# Processor.net
KiCad netlist of a schematic drawn in Altium Designer
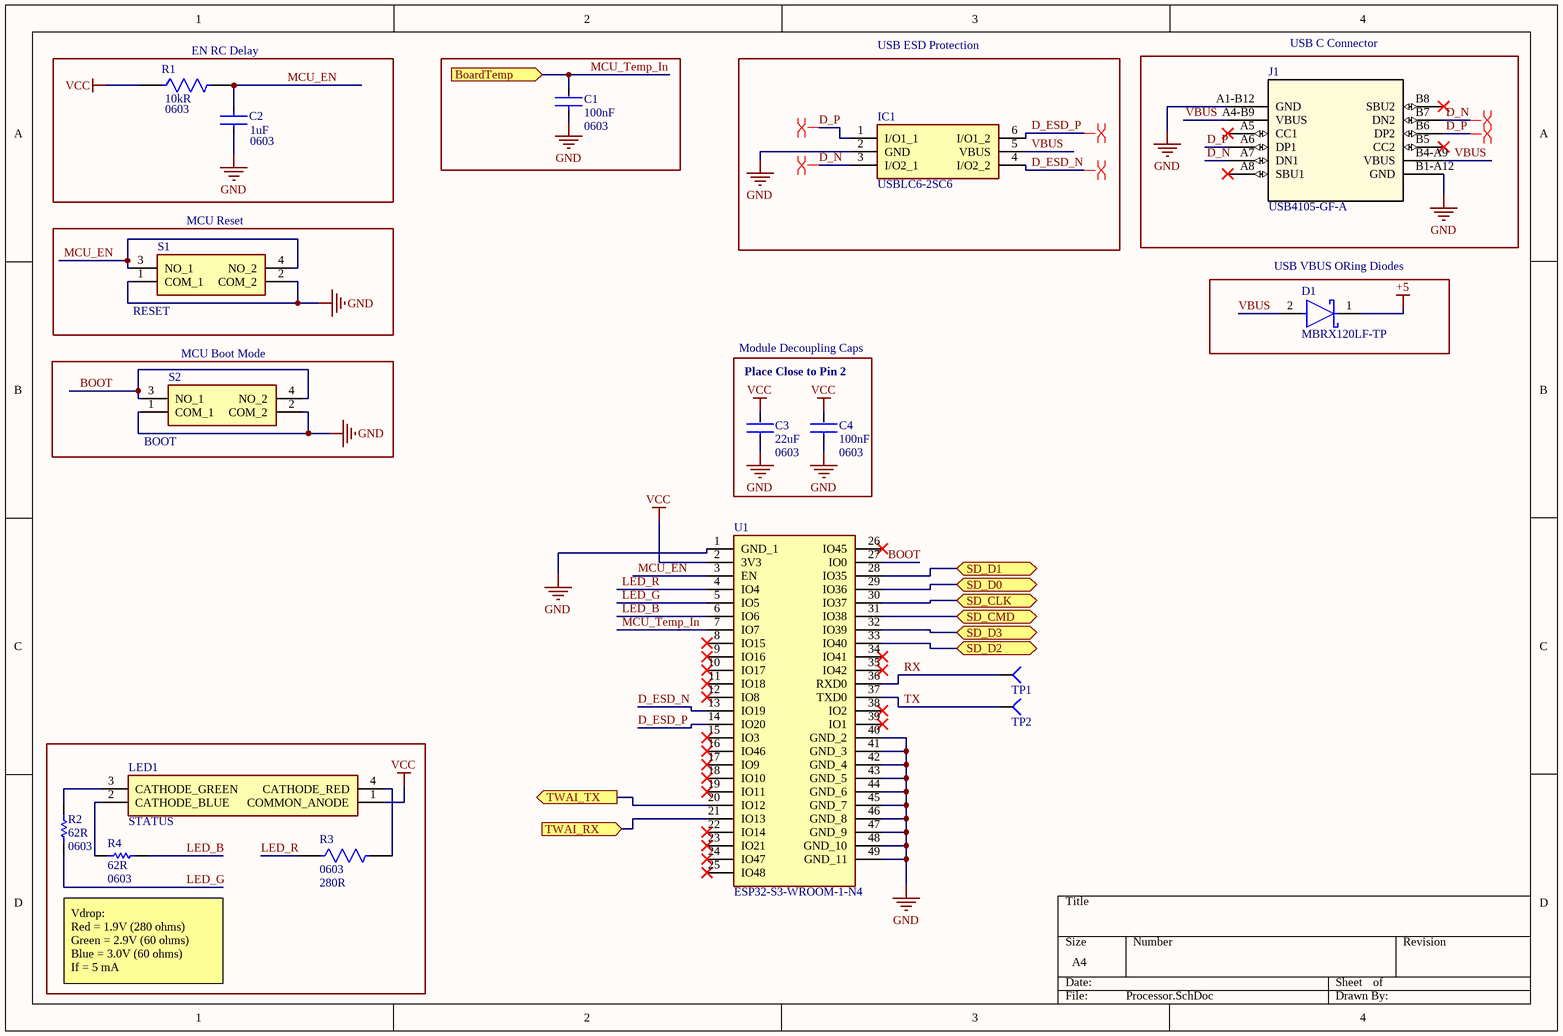
[diagram p0: Processor.SchDoc]

(export (version "E")
  (design (tool "Eeschema 10.0.6"))
  (components
    (comp (ref "C1")
      (value "CL10B104KB8WPNC")
      (footprint "FP-CL10-IPC_A")
      (description "Cap Ceramic 100nF 50V X7R ±10% Pad SMD 0603 +125°C T/R")
      (fields
        (field (name "CAPACITANCE") "100nF")
        (field (name "CASE/PACKAGE") "0603")
        (field (name "TOLERANCE") "10%")
      )
      (libsource (lib "Altium Content Vault") (part "b4654b650e69147ec39a6b967a45e02"))
    )
    (comp (ref "C2")
      (value "UMK107BJ105KA-T")
      (footprint "FP-0603-L_1_6_0_1-W_0_8_0-IPC_A")
      (description "None")
      (fields
        (field (name "TOLERANCE") "10%")
        (field (name "CASE/PACKAGE") "0603")
        (field (name "CAPACITANCE") "1uF")
      )
      (libsource (lib "Altium Content Vault") (part "02cd4be3c70576c341d710602a673aa"))
    )
    (comp (ref "C3")
      (value "GRM188R61A226ME15D")
      (footprint "FP-GRM188-0_2-IPC_C")
      (description "Chip Multilayer Ceramic Capacitors for General Purpose, 0603, 22uF, X5R, 15%, 20%, 10V")
      (fields
        (field (name "TOLERANCE") "20%")
        (field (name "CAPACITANCE") "22uF")
        (field (name "CASE CODE (IMPERIAL)") "0603")
      )
      (libsource (lib "Altium Content Vault") (part "11868f565c42a9108669ba33697ecf6"))
    )
    (comp (ref "C4")
      (value "CL10B104KB8WPNC")
      (footprint "FP-CL10-IPC_A")
      (description "Cap Ceramic 100nF 50V X7R ±10% Pad SMD 0603 +125°C T/R")
      (fields
        (field (name "CAPACITANCE") "100nF")
        (field (name "CASE/PACKAGE") "0603")
        (field (name "TOLERANCE") "10%")
      )
      (libsource (lib "Altium Content Vault") (part "b4654b650e69147ec39a6b967a45e02"))
    )
    (comp (ref "D1")
      (value "MBRX120LF-TP")
      (footprint "FP-SOD-123-IPC_A")
      (description "DIODE SCHOTTKY 20V 1A SOD123")
      (libsource (lib "Altium Content Vault") (part "1d6ec82d83fb6aee721767c19dac4b9"))
    )
    (comp (ref "IC1")
      (value "USBLC6-2SC6")
      (footprint "SOT95P280X145-6N")
      (description "Integrated Circuit")
      (fields (field (name "MOUSER PART NUMBER") "511-USBLC6-2SC6"))
      (libsource (lib "WiCAN_lib") (part "USBLC6-2SC6"))
    )
    (comp (ref "J1")
      (value "USB4105-GF-A")
      (footprint "USB4105_GCT")
      (description "No Description Available")
      (fields (field (name "COPYRIGHT") "Copyright (C) 2022 Ultra Librarian. All rights reserved."))
      (libsource (lib "WiCAN_lib") (part "USB4105-GF-A"))
    )
    (comp (ref "LED1")
      (value "STATUS")
      (footprint "CLMVCFKACL1D1L71BB7C3C3")
      (description "LED")
      (fields
        (field (name "MANUFACTURER_PART_NUMBER") "CLMVC-FKA-CL1D1L71BB7C3C3")
        (field (name "MOUSER PART NUMBER") "941-CLMVCFKACL1D1L71")
      )
      (libsource (lib "WiCAN_lib") (part "CLMVC-FKA-CL1D1L71BB7C3C3"))
    )
    (comp (ref "R1")
      (value "RMCF0603JG10K0")
      (footprint "FP-RMCF0603-MFG")
      (description "10kΩ ±5% 0.1W 0603 Thick Film Chip Resistor AEC-Q200 compliant")
      (fields
        (field (name "TOLERANCE") "5%")
        (field (name "CASE CODE (IMPERIAL)") "0603")
        (field (name "RESISTANCE") "10kR")
      )
      (libsource (lib "Altium Content Vault") (part "1029c3af85768c4190bb7ad29bc67b5"))
    )
    (comp (ref "R2")
      (value "ERJ-3GEYJ620V")
      (footprint "RESC1608X55X30ML15T15")
      (fields
        (field (name "MANUFACTURER") "Panasonic")
        (field (name "RESISTANCE") "62R")
        (field (name "PACKAGE") "0603")
      )
      (libsource (lib "Altium Content Vault") (part "RES"))
    )
    (comp (ref "R3")
      (value "RMCF0603FT280R")
      (footprint "FP-RMCF0603-MFG")
      (description "280Ω ±1% 0.1W 0603 Thick Film Chip Resistor AEC-Q200 compliant")
      (fields
        (field (name "CASE/PACKAGE") "0603")
        (field (name "TOLERANCE") "1%")
        (field (name "RESISTANCE") "280R")
      )
      (libsource (lib "Altium Content Vault") (part "1029c3af85768c4190bb7ad29bc67b5"))
    )
    (comp (ref "R4")
      (value "ERJ-3GEYJ620V")
      (footprint "RESC1608X55X30ML15T15")
      (fields
        (field (name "MANUFACTURER") "Panasonic")
        (field (name "RESISTANCE") "62R")
        (field (name "PACKAGE") "0603")
      )
      (libsource (lib "Altium Content Vault") (part "RES"))
    )
    (comp (ref "S1")
      (value "RESET")
      (footprint "PTS526SKG15SMTR2LFS")
      (description "Switch")
      (fields
        (field (name "MANUFACTURER_PART_NUMBER") "PTS526 SK08 SMTR2 LFS")
        (field (name "MOUSER PART NUMBER") "611-PTS526SK08SMTR2L")
      )
      (libsource (lib "WiCAN_lib") (part "PTS526_SK08_SMTR2_LFS"))
    )
    (comp (ref "S2")
      (value "BOOT")
      (footprint "PTS526SKG15SMTR2LFS")
      (description "Switch")
      (fields
        (field (name "MANUFACTURER_PART_NUMBER") "PTS526 SK08 SMTR2 LFS")
        (field (name "MOUSER PART NUMBER") "611-PTS526SK08SMTR2L")
      )
      (libsource (lib "WiCAN_lib") (part "PTS526_SK08_SMTR2_LFS"))
    )
    (comp (ref "TP1")
      (value "RX")
      (footprint "TESTPOINT_CIRCLE_1MM")
      (description "TESTPOINT 1MM CIRCLE")
      (libsource (lib "Connectors and Headers") (part "TESTPOINT_1MM_CIRCLE"))
    )
    (comp (ref "TP2")
      (value "TX")
      (footprint "TESTPOINT_CIRCLE_1MM")
      (description "TESTPOINT 1MM CIRCLE")
      (libsource (lib "Connectors and Headers") (part "TESTPOINT_1MM_CIRCLE"))
    )
    (comp (ref "U1")
      (value "ESP32-S3-WROOM-1-N4")
      (footprint "ESP32S3WROOM1N4")
      (description "Integrated Circuit")
      (fields (field (name "MOUSER PART NUMBER") "356-ESP32-S3WROOM1N4"))
      (libsource (lib "WiCAN_lib") (part "ESP32-S3-WROOM-1-N4"))
    )
  )
  (nets
    (net (code "1") (name "+5") (class "Default")
      (node (ref "D1") (pin "1") (pinfunction "C_1") (pintype "passive"))
    )
    (net (code "2") (name "/BOOT") (class "Default")
      (node (ref "S2") (pin "3") (pinfunction "NO_1_3") (pintype "passive"))
      (node (ref "S2") (pin "4") (pinfunction "NO_2_4") (pintype "passive"))
      (node (ref "U1") (pin "27") (pinfunction "IO0_27") (pintype "passive"))
    )
    (net (code "3") (name "/D_ESD_N") (class "Default")
      (node (ref "IC1") (pin "4") (pinfunction "I/O2_2_4") (pintype "passive"))
      (node (ref "U1") (pin "13") (pinfunction "IO19_13") (pintype "passive"))
    )
    (net (code "4") (name "/D_ESD_P") (class "Default")
      (node (ref "IC1") (pin "6") (pinfunction "I/O1_2_6") (pintype "passive"))
      (node (ref "U1") (pin "14") (pinfunction "IO20_14") (pintype "passive"))
    )
    (net (code "5") (name "/D_N") (class "Default")
      (node (ref "IC1") (pin "3") (pinfunction "I/O2_1_3") (pintype "passive"))
      (node (ref "J1") (pin "A7") (pinfunction "DN1_A7") (pintype "bidirectional"))
      (node (ref "J1") (pin "B7") (pinfunction "DN2_B7") (pintype "bidirectional"))
    )
    (net (code "6") (name "/D_P") (class "Default")
      (node (ref "IC1") (pin "1") (pinfunction "I/O1_1_1") (pintype "passive"))
      (node (ref "J1") (pin "A6") (pinfunction "DP1_A6") (pintype "bidirectional"))
      (node (ref "J1") (pin "B6") (pinfunction "DP2_B6") (pintype "bidirectional"))
    )
    (net (code "7") (name "/LED_B") (class "Default")
      (node (ref "R4") (pin "2") (pinfunction "2_2") (pintype "passive"))
      (node (ref "U1") (pin "6") (pinfunction "IO6_6") (pintype "passive"))
    )
    (net (code "8") (name "/LED_G") (class "Default")
      (node (ref "R2") (pin "2") (pinfunction "2_2") (pintype "passive"))
      (node (ref "U1") (pin "5") (pinfunction "IO5_5") (pintype "passive"))
    )
    (net (code "9") (name "/LED_R") (class "Default")
      (node (ref "R3") (pin "1") (pinfunction "1_1") (pintype "passive"))
      (node (ref "U1") (pin "4") (pinfunction "IO4_4") (pintype "passive"))
    )
    (net (code "10") (name "/MCU_EN") (class "Default")
      (node (ref "C2") (pin "1") (pinfunction "1_1") (pintype "passive"))
      (node (ref "R1") (pin "2") (pinfunction "2_2") (pintype "passive"))
      (node (ref "S1") (pin "3") (pinfunction "NO_1_3") (pintype "passive"))
      (node (ref "S1") (pin "4") (pinfunction "NO_2_4") (pintype "passive"))
      (node (ref "U1") (pin "3") (pinfunction "EN_3") (pintype "passive"))
    )
    (net (code "11") (name "/MCU_Temp_In") (class "Default")
      (node (ref "C1") (pin "2") (pinfunction "2_2") (pintype "passive"))
      (node (ref "U1") (pin "7") (pinfunction "IO7_7") (pintype "passive"))
    )
    (net (code "12") (name "/RX") (class "Default")
      (node (ref "TP1") (pin "1") (pinfunction "=value_1") (pintype "passive"))
      (node (ref "U1") (pin "36") (pinfunction "RXD0_36") (pintype "passive"))
    )
    (net (code "13") (name "/SD_CLK") (class "Default")
      (node (ref "U1") (pin "30") (pinfunction "IO37_30") (pintype "passive"))
    )
    (net (code "14") (name "/SD_CMD") (class "Default")
      (node (ref "U1") (pin "31") (pinfunction "IO38_31") (pintype "passive"))
    )
    (net (code "15") (name "/SD_D0") (class "Default")
      (node (ref "U1") (pin "29") (pinfunction "IO36_29") (pintype "passive"))
    )
    (net (code "16") (name "/SD_D1") (class "Default")
      (node (ref "U1") (pin "28") (pinfunction "IO35_28") (pintype "passive"))
    )
    (net (code "17") (name "/SD_D2") (class "Default")
      (node (ref "U1") (pin "33") (pinfunction "IO40_33") (pintype "passive"))
    )
    (net (code "18") (name "/SD_D3") (class "Default")
      (node (ref "U1") (pin "32") (pinfunction "IO39_32") (pintype "passive"))
    )
    (net (code "19") (name "/TWAI_RX") (class "Default")
      (node (ref "U1") (pin "21") (pinfunction "IO13_21") (pintype "passive"))
    )
    (net (code "20") (name "/TWAI_TX") (class "Default")
      (node (ref "U1") (pin "20") (pinfunction "IO12_20") (pintype "passive"))
    )
    (net (code "21") (name "/TX") (class "Default")
      (node (ref "TP2") (pin "1") (pinfunction "=value_1") (pintype "passive"))
      (node (ref "U1") (pin "37") (pinfunction "TXD0_37") (pintype "passive"))
    )
    (net (code "22") (name "/VBUS") (class "Default")
      (node (ref "D1") (pin "2") (pinfunction "A_2") (pintype "passive"))
      (node (ref "IC1") (pin "5") (pinfunction "VBUS_5") (pintype "passive"))
      (node (ref "J1") (pin "A4-B9") (pinfunction "VBUS_A4-B9") (pintype "power_in"))
      (node (ref "J1") (pin "B4-A9") (pinfunction "VBUS_B4-A9") (pintype "power_in"))
    )
    (net (code "23") (name "GND") (class "Default")
      (node (ref "C1") (pin "1") (pinfunction "1_1") (pintype "passive"))
      (node (ref "C2") (pin "2") (pinfunction "2_2") (pintype "passive"))
      (node (ref "C3") (pin "1") (pinfunction "1_1") (pintype "passive"))
      (node (ref "C4") (pin "1") (pinfunction "1_1") (pintype "passive"))
      (node (ref "IC1") (pin "2") (pinfunction "GND_2") (pintype "passive"))
      (node (ref "J1") (pin "A1-B12") (pinfunction "GND_A1-B12") (pintype "passive"))
      (node (ref "J1") (pin "B1-A12") (pinfunction "GND_B1-A12") (pintype "passive"))
      (node (ref "S1") (pin "1") (pinfunction "COM_1_1") (pintype "passive"))
      (node (ref "S1") (pin "2") (pinfunction "COM_2_2") (pintype "passive"))
      (node (ref "S2") (pin "1") (pinfunction "COM_1_1") (pintype "passive"))
      (node (ref "S2") (pin "2") (pinfunction "COM_2_2") (pintype "passive"))
      (node (ref "U1") (pin "1") (pinfunction "GND_1_1") (pintype "passive"))
      (node (ref "U1") (pin "40") (pinfunction "GND_2_40") (pintype "passive"))
      (node (ref "U1") (pin "41") (pinfunction "GND_3_41") (pintype "passive"))
      (node (ref "U1") (pin "42") (pinfunction "GND_4_42") (pintype "passive"))
      (node (ref "U1") (pin "43") (pinfunction "GND_5_43") (pintype "passive"))
      (node (ref "U1") (pin "44") (pinfunction "GND_6_44") (pintype "passive"))
      (node (ref "U1") (pin "45") (pinfunction "GND_7_45") (pintype "passive"))
      (node (ref "U1") (pin "46") (pinfunction "GND_8_46") (pintype "passive"))
      (node (ref "U1") (pin "47") (pinfunction "GND_9_47") (pintype "passive"))
      (node (ref "U1") (pin "48") (pinfunction "GND_10_48") (pintype "passive"))
      (node (ref "U1") (pin "49") (pinfunction "GND_11_49") (pintype "passive"))
    )
    (net (code "24") (name "Net-(LED1-CATHODE_BLUE)") (class "Default")
      (node (ref "LED1") (pin "2") (pinfunction "CATHODE_BLUE_2") (pintype "passive"))
      (node (ref "R4") (pin "1") (pinfunction "1_1") (pintype "passive"))
    )
    (net (code "25") (name "Net-(LED1-CATHODE_GREEN)") (class "Default")
      (node (ref "LED1") (pin "3") (pinfunction "CATHODE_GREEN_3") (pintype "passive"))
      (node (ref "R2") (pin "1") (pinfunction "1_1") (pintype "passive"))
    )
    (net (code "26") (name "Net-(LED1-CATHODE_RED)") (class "Default")
      (node (ref "LED1") (pin "4") (pinfunction "CATHODE_RED_4") (pintype "passive"))
      (node (ref "R3") (pin "2") (pinfunction "2_2") (pintype "passive"))
    )
    (net (code "27") (name "VCC") (class "Default")
      (node (ref "C3") (pin "2") (pinfunction "2_2") (pintype "passive"))
      (node (ref "C4") (pin "2") (pinfunction "2_2") (pintype "passive"))
      (node (ref "LED1") (pin "1") (pinfunction "COMMON_ANODE_1") (pintype "passive"))
      (node (ref "R1") (pin "1") (pinfunction "1_1") (pintype "passive"))
      (node (ref "U1") (pin "2") (pinfunction "3V3_2") (pintype "passive"))
    )
    (net (code "28") (name "unconnected-(J1-CC1-PadA5)") (class "Default")
      (node (ref "J1") (pin "A5") (pinfunction "CC1_A5") (pintype "bidirectional+no_connect"))
    )
    (net (code "29") (name "unconnected-(J1-CC2-PadB5)") (class "Default")
      (node (ref "J1") (pin "B5") (pinfunction "CC2_B5") (pintype "bidirectional+no_connect"))
    )
    (net (code "30") (name "unconnected-(J1-SBU1-PadA8)") (class "Default")
      (node (ref "J1") (pin "A8") (pinfunction "SBU1_A8") (pintype "bidirectional+no_connect"))
    )
    (net (code "31") (name "unconnected-(J1-SBU2-PadB8)") (class "Default")
      (node (ref "J1") (pin "B8") (pinfunction "SBU2_B8") (pintype "bidirectional+no_connect"))
    )
    (net (code "32") (name "unconnected-(U1-IO1-Pad39)") (class "Default")
      (node (ref "U1") (pin "39") (pinfunction "IO1_39") (pintype "passive+no_connect"))
    )
    (net (code "33") (name "unconnected-(U1-IO2-Pad38)") (class "Default")
      (node (ref "U1") (pin "38") (pinfunction "IO2_38") (pintype "passive+no_connect"))
    )
    (net (code "34") (name "unconnected-(U1-IO3-Pad15)") (class "Default")
      (node (ref "U1") (pin "15") (pinfunction "IO3_15") (pintype "passive+no_connect"))
    )
    (net (code "35") (name "unconnected-(U1-IO8-Pad12)") (class "Default")
      (node (ref "U1") (pin "12") (pinfunction "IO8_12") (pintype "passive+no_connect"))
    )
    (net (code "36") (name "unconnected-(U1-IO9-Pad17)") (class "Default")
      (node (ref "U1") (pin "17") (pinfunction "IO9_17") (pintype "passive+no_connect"))
    )
    (net (code "37") (name "unconnected-(U1-IO10-Pad18)") (class "Default")
      (node (ref "U1") (pin "18") (pinfunction "IO10_18") (pintype "passive+no_connect"))
    )
    (net (code "38") (name "unconnected-(U1-IO11-Pad19)") (class "Default")
      (node (ref "U1") (pin "19") (pinfunction "IO11_19") (pintype "passive"))
    )
    (net (code "39") (name "unconnected-(U1-IO14-Pad22)") (class "Default")
      (node (ref "U1") (pin "22") (pinfunction "IO14_22") (pintype "passive+no_connect"))
    )
    (net (code "40") (name "unconnected-(U1-IO15-Pad8)") (class "Default")
      (node (ref "U1") (pin "8") (pinfunction "IO15_8") (pintype "passive+no_connect"))
    )
    (net (code "41") (name "unconnected-(U1-IO16-Pad9)") (class "Default")
      (node (ref "U1") (pin "9") (pinfunction "IO16_9") (pintype "passive+no_connect"))
    )
    (net (code "42") (name "unconnected-(U1-IO17-Pad10)") (class "Default")
      (node (ref "U1") (pin "10") (pinfunction "IO17_10") (pintype "passive+no_connect"))
    )
    (net (code "43") (name "unconnected-(U1-IO18-Pad11)") (class "Default")
      (node (ref "U1") (pin "11") (pinfunction "IO18_11") (pintype "passive+no_connect"))
    )
    (net (code "44") (name "unconnected-(U1-IO21-Pad23)") (class "Default")
      (node (ref "U1") (pin "23") (pinfunction "IO21_23") (pintype "passive+no_connect"))
    )
    (net (code "45") (name "unconnected-(U1-IO41-Pad34)") (class "Default")
      (node (ref "U1") (pin "34") (pinfunction "IO41_34") (pintype "passive+no_connect"))
    )
    (net (code "46") (name "unconnected-(U1-IO42-Pad35)") (class "Default")
      (node (ref "U1") (pin "35") (pinfunction "IO42_35") (pintype "passive+no_connect"))
    )
    (net (code "47") (name "unconnected-(U1-IO45-Pad26)") (class "Default")
      (node (ref "U1") (pin "26") (pinfunction "IO45_26") (pintype "passive+no_connect"))
    )
    (net (code "48") (name "unconnected-(U1-IO46-Pad16)") (class "Default")
      (node (ref "U1") (pin "16") (pinfunction "IO46_16") (pintype "passive+no_connect"))
    )
    (net (code "49") (name "unconnected-(U1-IO47-Pad24)") (class "Default")
      (node (ref "U1") (pin "24") (pinfunction "IO47_24") (pintype "passive+no_connect"))
    )
    (net (code "50") (name "unconnected-(U1-IO48-Pad25)") (class "Default")
      (node (ref "U1") (pin "25") (pinfunction "IO48_25") (pintype "passive+no_connect"))
    )
  )
)
